# ClockSure.net
KiCad netlist of a schematic drawn in EAGLE
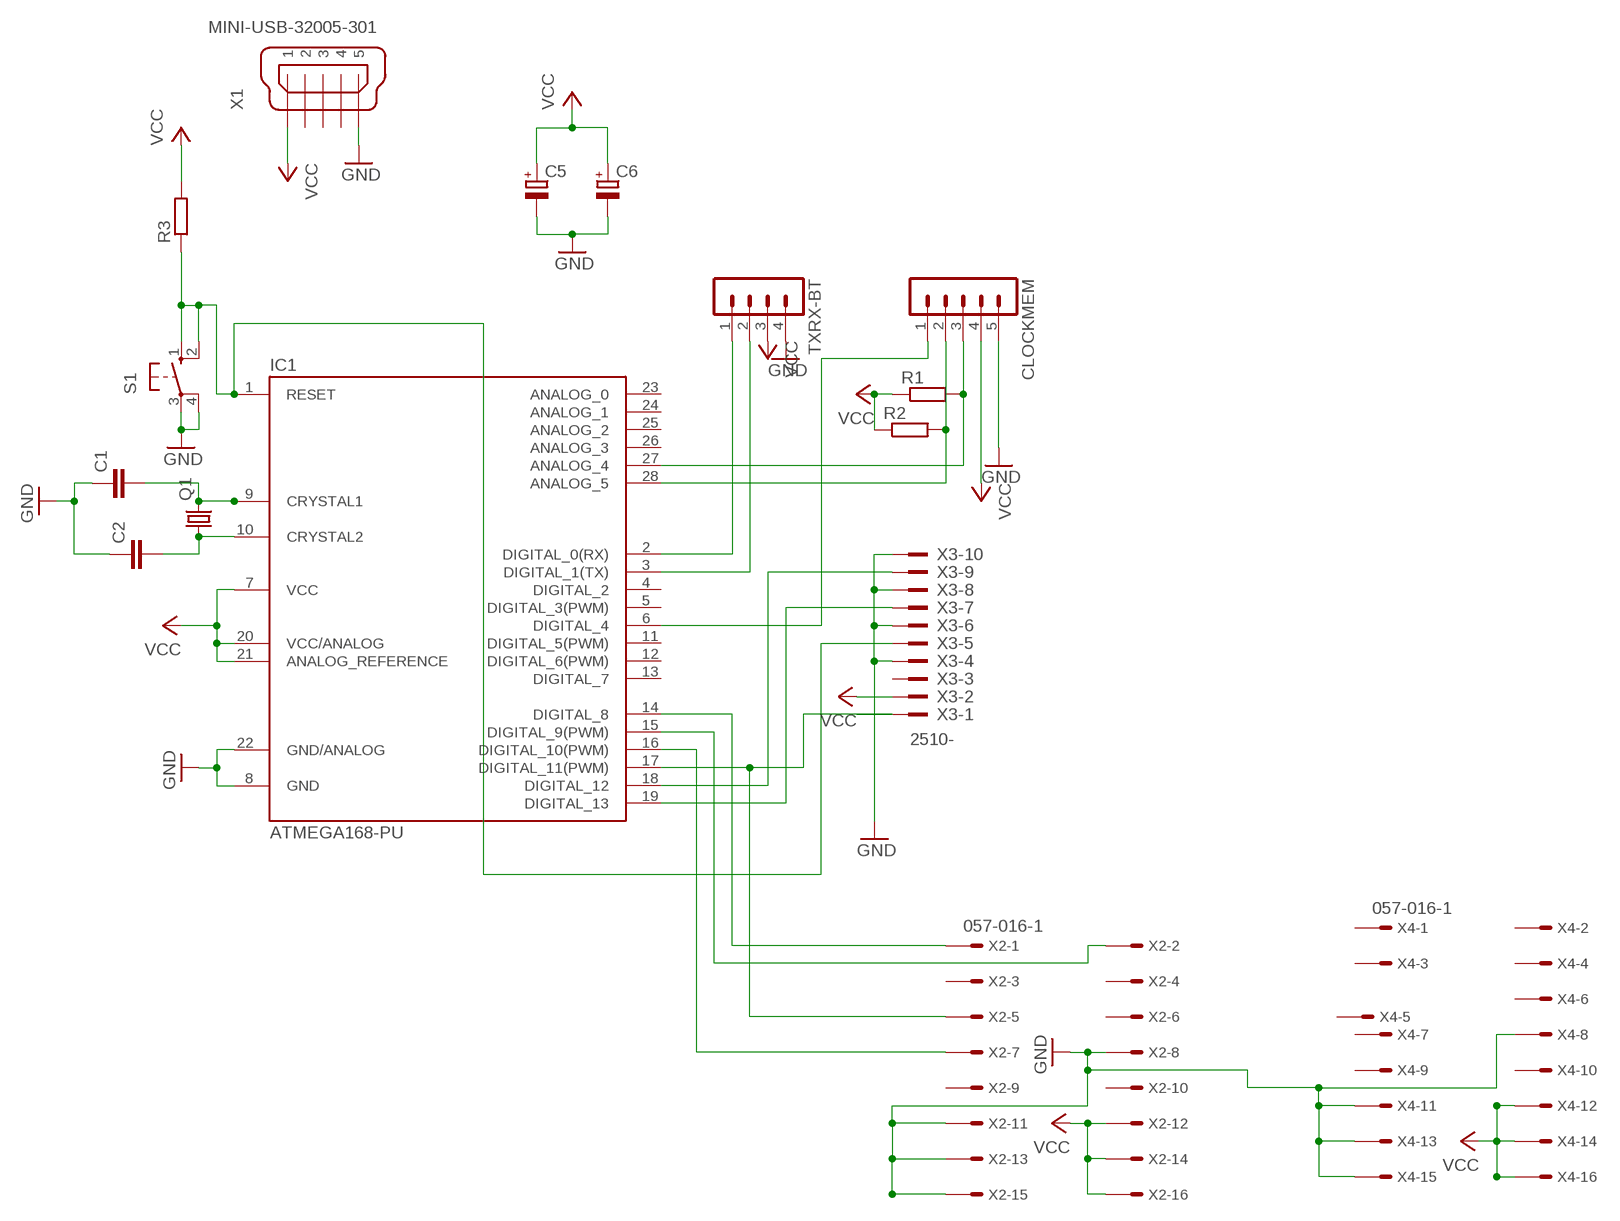
[diagram p0: schematic, sheet 1]

(export (version "E")
  (design (tool "Eeschema 10.0.6"))
  (components
    (comp (ref "C1")
      (value "C-EU025-030X050")
      (footprint "eagle-import:C025-030X050")
      (libsource (lib "eagle-import") (part "C-EU025-030X050"))
    )
    (comp (ref "C2")
      (value "C-EU025-030X050")
      (footprint "eagle-import:C025-030X050")
      (libsource (lib "eagle-import") (part "C-EU025-030X050"))
    )
    (comp (ref "C5")
      (value "CPOL-EUE2.5-6")
      (footprint "eagle-import:E2,5-6")
      (libsource (lib "eagle-import") (part "CPOL-EUE2.5-6"))
    )
    (comp (ref "C6")
      (value "CPOL-EUE2.5-6")
      (footprint "eagle-import:E2,5-6")
      (libsource (lib "eagle-import") (part "CPOL-EUE2.5-6"))
    )
    (comp (ref "CLOCKMEM")
      (value "MA05-1")
      (footprint "eagle-import:MA05-1")
      (libsource (lib "eagle-import") (part "MA05-1"))
    )
    (comp (ref "IC1")
      (value "ATMEGA168-PU")
      (footprint "eagle-import:DIL28-3")
      (libsource (lib "eagle-import") (part "ATMEGA168-PU"))
    )
    (comp (ref "Q1")
      (value "CRYSTALHC49U70")
      (footprint "eagle-import:HC49U70")
      (libsource (lib "eagle-import") (part "CRYSTALHC49U70"))
    )
    (comp (ref "R1")
      (value "R-EU_0207/10")
      (footprint "eagle-import:0207_10")
      (libsource (lib "eagle-import") (part "R-EU_0207/10"))
    )
    (comp (ref "R2")
      (value "R-EU_0207/10")
      (footprint "eagle-import:0207_10")
      (libsource (lib "eagle-import") (part "R-EU_0207/10"))
    )
    (comp (ref "R3")
      (value "R-EU_0207/10")
      (footprint "eagle-import:0207_10")
      (libsource (lib "eagle-import") (part "R-EU_0207/10"))
    )
    (comp (ref "S1")
      (value "10-XX")
      (footprint "eagle-import:B3F-10XX")
      (fields (field (name "MPN") "B3F-1000"))
      (libsource (lib "eagle-import") (part "10-XX"))
    )
    (comp (ref "TXRX-BT")
      (value "MA04-1")
      (footprint "eagle-import:MA04-1")
      (libsource (lib "eagle-import") (part "MA04-1"))
    )
    (comp (ref "X1")
      (value "MINI-USB-32005-301")
      (footprint "eagle-import:32005-301")
      (libsource (lib "eagle-import") (part "MINI-USB-32005-301"))
    )
    (comp (ref "X2")
      (value "057-016-1")
      (footprint "eagle-import:057-016-1")
      (libsource (lib "eagle-import") (part "057-016-1"))
    )
    (comp (ref "X3")
      (value "2510-")
      (footprint "eagle-import:PAK100_2500-10")
      (fields (field (name "MF") "3M") (field (name "MPN") "2510-6002UB"))
      (libsource (lib "eagle-import") (part "2510-"))
    )
    (comp (ref "X4")
      (value "057-016-1")
      (footprint "eagle-import:057-016-1")
      (fields (field (name "OC_FARNELL") "unknown") (field (name "OC_NEWARK") "unknown"))
      (libsource (lib "eagle-import") (part "057-016-1"))
    )
  )
  (nets
    (net (code "1") (name "GND") (class "Default")
      (node (ref "C1") (pin "1") (pinfunction "1_1") (pintype "passive"))
      (node (ref "C2") (pin "1") (pinfunction "1_1") (pintype "passive"))
      (node (ref "C5") (pin "-") (pinfunction "-_-") (pintype "passive"))
      (node (ref "C6") (pin "-") (pinfunction "-_-") (pintype "passive"))
      (node (ref "CLOCKMEM") (pin "5") (pinfunction "5_5") (pintype "passive"))
      (node (ref "IC1") (pin "22") (pinfunction "GND/ANALOG_22") (pintype "power_in"))
      (node (ref "IC1") (pin "8") (pinfunction "GND_8") (pintype "power_in"))
      (node (ref "S1") (pin "3") (pinfunction "P_3") (pintype "passive"))
      (node (ref "S1") (pin "4") (pinfunction "P1_4") (pintype "passive"))
      (node (ref "TXRX-BT") (pin "4") (pinfunction "4_4") (pintype "passive"))
      (node (ref "X1") (pin "5") (pinfunction "5_5") (pintype "passive"))
      (node (ref "X2") (pin "11") (pinfunction "S_11") (pintype "passive"))
      (node (ref "X2") (pin "13") (pinfunction "S_13") (pintype "passive"))
      (node (ref "X2") (pin "15") (pinfunction "S_15") (pintype "passive"))
      (node (ref "X2") (pin "8") (pinfunction "S_8") (pintype "passive"))
      (node (ref "X3") (pin "10") (pinfunction "KL_10") (pintype "passive"))
      (node (ref "X3") (pin "4") (pinfunction "KL_4") (pintype "passive"))
      (node (ref "X3") (pin "6") (pinfunction "KL_6") (pintype "passive"))
      (node (ref "X3") (pin "8") (pinfunction "KL_8") (pintype "passive"))
      (node (ref "X4") (pin "11") (pinfunction "S_11") (pintype "passive"))
      (node (ref "X4") (pin "13") (pinfunction "S_13") (pintype "passive"))
      (node (ref "X4") (pin "15") (pinfunction "S_15") (pintype "passive"))
      (node (ref "X4") (pin "8") (pinfunction "S_8") (pintype "passive"))
    )
    (net (code "2") (name "Net-(IC1-ANALOG_4)") (class "Default")
      (node (ref "CLOCKMEM") (pin "3") (pinfunction "3_3") (pintype "passive"))
      (node (ref "IC1") (pin "27") (pinfunction "ANALOG_4_27") (pintype "bidirectional"))
      (node (ref "R1") (pin "2") (pinfunction "2_2") (pintype "passive"))
    )
    (net (code "3") (name "Net-(IC1-ANALOG_5)") (class "Default")
      (node (ref "CLOCKMEM") (pin "2") (pinfunction "2_2") (pintype "passive"))
      (node (ref "IC1") (pin "28") (pinfunction "ANALOG_5_28") (pintype "bidirectional"))
      (node (ref "R2") (pin "2") (pinfunction "2_2") (pintype "passive"))
    )
    (net (code "4") (name "Net-(IC1-CRYSTAL1)") (class "Default")
      (node (ref "C1") (pin "2") (pinfunction "2_2") (pintype "passive"))
      (node (ref "IC1") (pin "9") (pinfunction "CRYSTAL1_9") (pintype "bidirectional"))
      (node (ref "Q1") (pin "2") (pinfunction "2_2") (pintype "passive"))
    )
    (net (code "5") (name "Net-(IC1-CRYSTAL2)") (class "Default")
      (node (ref "C2") (pin "2") (pinfunction "2_2") (pintype "passive"))
      (node (ref "IC1") (pin "10") (pinfunction "CRYSTAL2_10") (pintype "bidirectional"))
      (node (ref "Q1") (pin "1") (pinfunction "1_1") (pintype "passive"))
    )
    (net (code "6") (name "Net-(IC1-DIGITAL_0(RX))") (class "Default")
      (node (ref "IC1") (pin "2") (pinfunction "DIGITAL_0(RX)_2") (pintype "bidirectional"))
      (node (ref "TXRX-BT") (pin "1") (pinfunction "1_1") (pintype "passive"))
    )
    (net (code "7") (name "Net-(IC1-DIGITAL_1(TX))") (class "Default")
      (node (ref "IC1") (pin "3") (pinfunction "DIGITAL_1(TX)_3") (pintype "bidirectional"))
      (node (ref "TXRX-BT") (pin "2") (pinfunction "2_2") (pintype "passive"))
    )
    (net (code "8") (name "Net-(IC1-DIGITAL_4)") (class "Default")
      (node (ref "CLOCKMEM") (pin "1") (pinfunction "1_1") (pintype "passive"))
      (node (ref "IC1") (pin "6") (pinfunction "DIGITAL_4_6") (pintype "bidirectional"))
    )
    (net (code "9") (name "Net-(IC1-DIGITAL_8)") (class "Default")
      (node (ref "IC1") (pin "14") (pinfunction "DIGITAL_8_14") (pintype "bidirectional"))
      (node (ref "X2") (pin "1") (pinfunction "S_1") (pintype "passive"))
    )
    (net (code "10") (name "Net-(IC1-DIGITAL_9(PWM))") (class "Default")
      (node (ref "IC1") (pin "15") (pinfunction "DIGITAL_9(PWM)_15") (pintype "bidirectional"))
      (node (ref "X2") (pin "2") (pinfunction "S_2") (pintype "passive"))
    )
    (net (code "11") (name "Net-(IC1-DIGITAL_10(PWM))") (class "Default")
      (node (ref "IC1") (pin "16") (pinfunction "DIGITAL_10(PWM)_16") (pintype "bidirectional"))
      (node (ref "X2") (pin "7") (pinfunction "S_7") (pintype "passive"))
    )
    (net (code "12") (name "Net-(IC1-DIGITAL_11(PWM))") (class "Default")
      (node (ref "IC1") (pin "17") (pinfunction "DIGITAL_11(PWM)_17") (pintype "bidirectional"))
      (node (ref "X2") (pin "5") (pinfunction "S_5") (pintype "passive"))
      (node (ref "X3") (pin "1") (pinfunction "KL_1") (pintype "passive"))
    )
    (net (code "13") (name "Net-(IC1-DIGITAL_12)") (class "Default")
      (node (ref "IC1") (pin "18") (pinfunction "DIGITAL_12_18") (pintype "bidirectional"))
      (node (ref "X3") (pin "9") (pinfunction "KL_9") (pintype "passive"))
    )
    (net (code "14") (name "Net-(IC1-DIGITAL_13)") (class "Default")
      (node (ref "IC1") (pin "19") (pinfunction "DIGITAL_13_19") (pintype "bidirectional"))
      (node (ref "X3") (pin "7") (pinfunction "KL_7") (pintype "passive"))
    )
    (net (code "15") (name "Net-(IC1-RESET)") (class "Default")
      (node (ref "IC1") (pin "1") (pinfunction "RESET_1") (pintype "bidirectional"))
      (node (ref "R3") (pin "1") (pinfunction "1_1") (pintype "passive"))
      (node (ref "S1") (pin "1") (pinfunction "S_1") (pintype "passive"))
      (node (ref "S1") (pin "2") (pinfunction "S1_2") (pintype "passive"))
      (node (ref "X3") (pin "5") (pinfunction "KL_5") (pintype "passive"))
    )
    (net (code "16") (name "VCC") (class "Default")
      (node (ref "C5") (pin "+") (pinfunction "+_+") (pintype "passive"))
      (node (ref "C6") (pin "+") (pinfunction "+_+") (pintype "passive"))
      (node (ref "CLOCKMEM") (pin "4") (pinfunction "4_4") (pintype "passive"))
      (node (ref "IC1") (pin "20") (pinfunction "VCC/ANALOG_20") (pintype "passive"))
      (node (ref "IC1") (pin "21") (pinfunction "ANALOG_REFERENCE_21") (pintype "passive"))
      (node (ref "IC1") (pin "7") (pinfunction "VCC_7") (pintype "power_in"))
      (node (ref "R1") (pin "1") (pinfunction "1_1") (pintype "passive"))
      (node (ref "R2") (pin "1") (pinfunction "1_1") (pintype "passive"))
      (node (ref "R3") (pin "2") (pinfunction "2_2") (pintype "passive"))
      (node (ref "TXRX-BT") (pin "3") (pinfunction "3_3") (pintype "passive"))
      (node (ref "X1") (pin "1") (pinfunction "1_1") (pintype "passive"))
      (node (ref "X2") (pin "12") (pinfunction "S_12") (pintype "passive"))
      (node (ref "X2") (pin "14") (pinfunction "S_14") (pintype "passive"))
      (node (ref "X2") (pin "16") (pinfunction "S_16") (pintype "passive"))
      (node (ref "X3") (pin "2") (pinfunction "KL_2") (pintype "passive"))
      (node (ref "X4") (pin "12") (pinfunction "S_12") (pintype "passive"))
      (node (ref "X4") (pin "14") (pinfunction "S_14") (pintype "passive"))
      (node (ref "X4") (pin "16") (pinfunction "S_16") (pintype "passive"))
    )
    (net (code "17") (name "unconnected-(IC1-ANALOG_0-Pad23)") (class "Default")
      (node (ref "IC1") (pin "23") (pinfunction "ANALOG_0_23") (pintype "bidirectional"))
    )
    (net (code "18") (name "unconnected-(IC1-ANALOG_1-Pad24)") (class "Default")
      (node (ref "IC1") (pin "24") (pinfunction "ANALOG_1_24") (pintype "bidirectional"))
    )
    (net (code "19") (name "unconnected-(IC1-ANALOG_2-Pad25)") (class "Default")
      (node (ref "IC1") (pin "25") (pinfunction "ANALOG_2_25") (pintype "bidirectional"))
    )
    (net (code "20") (name "unconnected-(IC1-ANALOG_3-Pad26)") (class "Default")
      (node (ref "IC1") (pin "26") (pinfunction "ANALOG_3_26") (pintype "bidirectional"))
    )
    (net (code "21") (name "unconnected-(IC1-DIGITAL_2-Pad4)") (class "Default")
      (node (ref "IC1") (pin "4") (pinfunction "DIGITAL_2_4") (pintype "bidirectional"))
    )
    (net (code "22") (name "unconnected-(IC1-DIGITAL_3(PWM)-Pad5)") (class "Default")
      (node (ref "IC1") (pin "5") (pinfunction "DIGITAL_3(PWM)_5") (pintype "bidirectional"))
    )
    (net (code "23") (name "unconnected-(IC1-DIGITAL_5(PWM)-Pad11)") (class "Default")
      (node (ref "IC1") (pin "11") (pinfunction "DIGITAL_5(PWM)_11") (pintype "bidirectional"))
    )
    (net (code "24") (name "unconnected-(IC1-DIGITAL_6(PWM)-Pad12)") (class "Default")
      (node (ref "IC1") (pin "12") (pinfunction "DIGITAL_6(PWM)_12") (pintype "bidirectional"))
    )
    (net (code "25") (name "unconnected-(IC1-DIGITAL_7-Pad13)") (class "Default")
      (node (ref "IC1") (pin "13") (pinfunction "DIGITAL_7_13") (pintype "bidirectional"))
    )
    (net (code "26") (name "unconnected-(X1-Pad2)") (class "Default")
      (node (ref "X1") (pin "2") (pinfunction "2_2") (pintype "passive"))
    )
    (net (code "27") (name "unconnected-(X1-Pad3)") (class "Default")
      (node (ref "X1") (pin "3") (pinfunction "3_3") (pintype "passive"))
    )
    (net (code "28") (name "unconnected-(X1-Pad4)") (class "Default")
      (node (ref "X1") (pin "4") (pinfunction "4_4") (pintype "passive"))
    )
    (net (code "29") (name "unconnected-(X2B-S-Pad10)") (class "Default")
      (node (ref "X2") (pin "10") (pinfunction "S_10") (pintype "passive"))
    )
    (net (code "30") (name "unconnected-(X2J-S-Pad3)") (class "Default")
      (node (ref "X2") (pin "3") (pinfunction "S_3") (pintype "passive"))
    )
    (net (code "31") (name "unconnected-(X2K-S-Pad4)") (class "Default")
      (node (ref "X2") (pin "4") (pinfunction "S_4") (pintype "passive"))
    )
    (net (code "32") (name "unconnected-(X2M-S-Pad6)") (class "Default")
      (node (ref "X2") (pin "6") (pinfunction "S_6") (pintype "passive"))
    )
    (net (code "33") (name "unconnected-(X2P-S-Pad9)") (class "Default")
      (node (ref "X2") (pin "9") (pinfunction "S_9") (pintype "passive"))
    )
    (net (code "34") (name "unconnected-(X3D-KL-Pad3)") (class "Default")
      (node (ref "X3") (pin "3") (pinfunction "KL_3") (pintype "passive"))
    )
    (net (code "35") (name "unconnected-(X4A-S-Pad1)") (class "Default")
      (node (ref "X4") (pin "1") (pinfunction "S_1") (pintype "passive"))
    )
    (net (code "36") (name "unconnected-(X4B-S-Pad10)") (class "Default")
      (node (ref "X4") (pin "10") (pinfunction "S_10") (pintype "passive"))
    )
    (net (code "37") (name "unconnected-(X4I-S-Pad2)") (class "Default")
      (node (ref "X4") (pin "2") (pinfunction "S_2") (pintype "passive"))
    )
    (net (code "38") (name "unconnected-(X4J-S-Pad3)") (class "Default")
      (node (ref "X4") (pin "3") (pinfunction "S_3") (pintype "passive"))
    )
    (net (code "39") (name "unconnected-(X4K-S-Pad4)") (class "Default")
      (node (ref "X4") (pin "4") (pinfunction "S_4") (pintype "passive"))
    )
    (net (code "40") (name "unconnected-(X4L-S-Pad5)") (class "Default")
      (node (ref "X4") (pin "5") (pinfunction "S_5") (pintype "passive"))
    )
    (net (code "41") (name "unconnected-(X4M-S-Pad6)") (class "Default")
      (node (ref "X4") (pin "6") (pinfunction "S_6") (pintype "passive"))
    )
    (net (code "42") (name "unconnected-(X4N-S-Pad7)") (class "Default")
      (node (ref "X4") (pin "7") (pinfunction "S_7") (pintype "passive"))
    )
    (net (code "43") (name "unconnected-(X4P-S-Pad9)") (class "Default")
      (node (ref "X4") (pin "9") (pinfunction "S_9") (pintype "passive"))
    )
  )
)
